# FLASHLIGHT_MAIN_SCH.net
KiCad netlist of a schematic drawn in Altium Designer
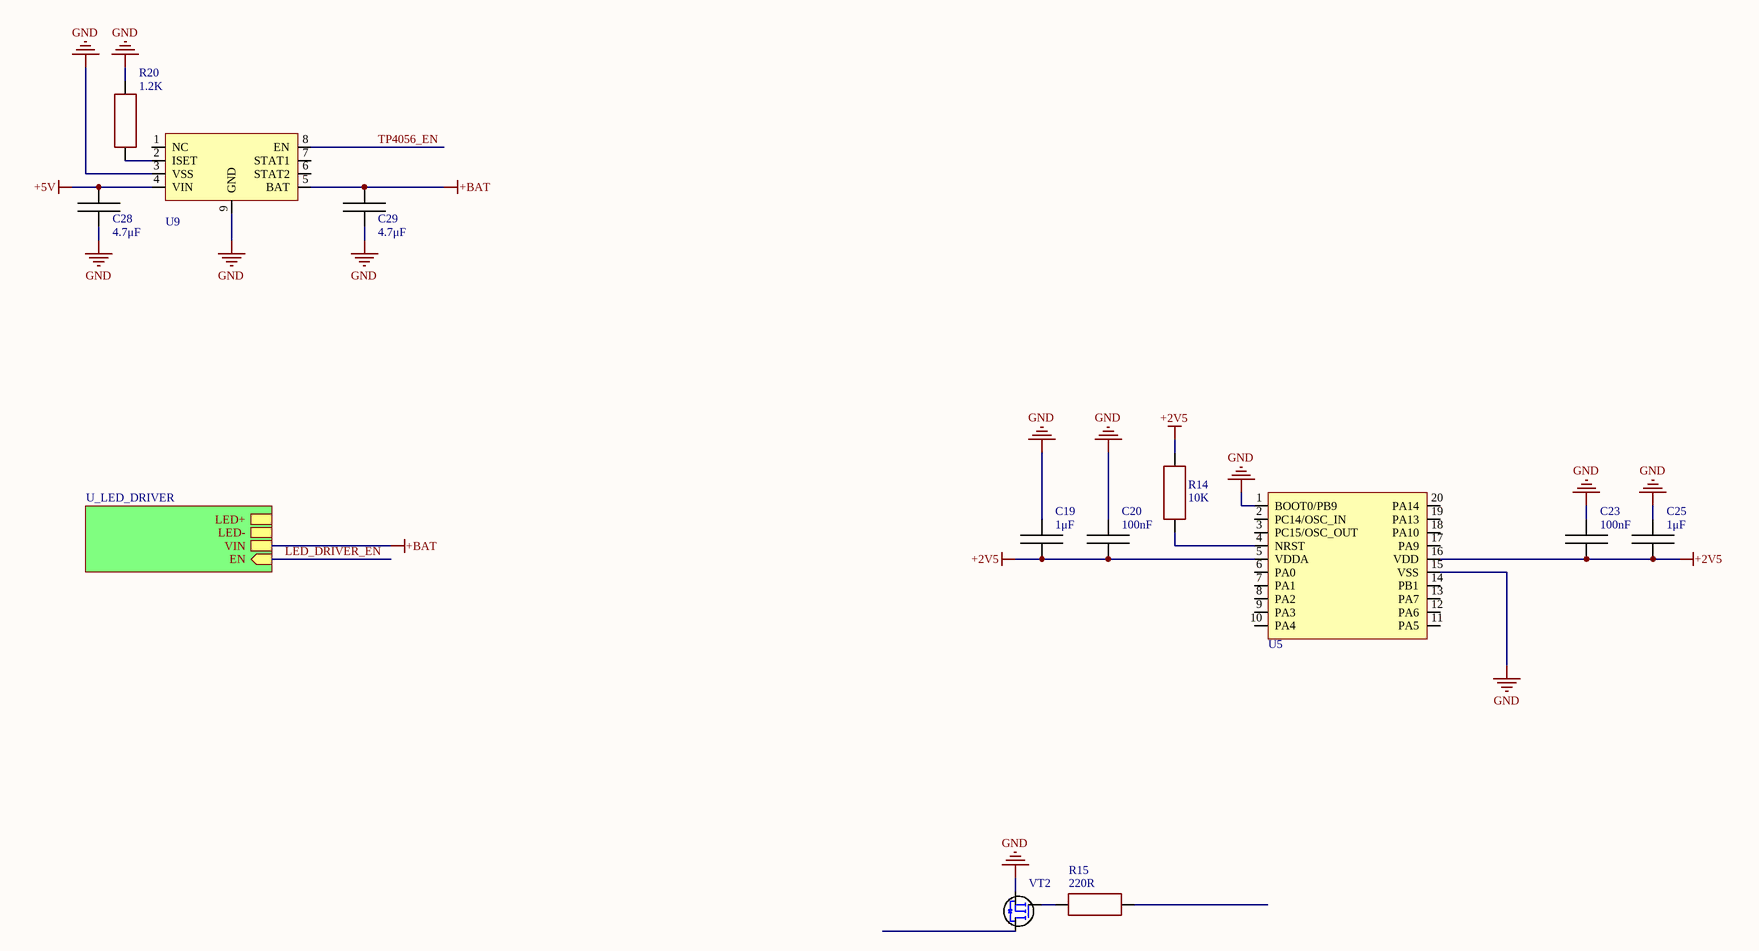
[diagram p0: FLASHLIGHT_MAIN_SCH.SchDoc]

(export (version "E")
  (design (tool "Eeschema 10.0.6"))
  (components
    (comp (ref "C19")
      (value "1μF")
      (footprint "CAP: 0402")
      (fields (field (name "VOLTAGE") "??V") (field (name "Comment") "Cap_0402"))
      (libsource (lib "capacitor") (part "Cap_0402"))
    )
    (comp (ref "C20")
      (value "100nF")
      (footprint "CAP: 0402")
      (fields (field (name "VOLTAGE") "??V") (field (name "Comment") "Cap_0402"))
      (libsource (lib "capacitor") (part "Cap_0402"))
    )
    (comp (ref "C23")
      (value "100nF")
      (footprint "CAP: 0402")
      (fields (field (name "VOLTAGE") "??V") (field (name "Comment") "Cap_0402"))
      (libsource (lib "capacitor") (part "Cap_0402"))
    )
    (comp (ref "C25")
      (value "1μF")
      (footprint "CAP: 0402")
      (fields (field (name "VOLTAGE") "??V") (field (name "Comment") "Cap_0402"))
      (libsource (lib "capacitor") (part "Cap_0402"))
    )
    (comp (ref "C28")
      (value "4.7μF")
      (footprint "CAP: 0402")
      (fields (field (name "VOLTAGE") "X5R 6.3В 20%") (field (name "Comment") "Cap_0402"))
      (libsource (lib "capacitor") (part "Cap_0402"))
    )
    (comp (ref "C29")
      (value "4.7μF")
      (footprint "CAP: 0402")
      (fields (field (name "VOLTAGE") "X5R 6.3В 20%") (field (name "Comment") "Cap_0402"))
      (libsource (lib "capacitor") (part "Cap_0402"))
    )
    (comp (ref "R14")
      (value "10K")
      (footprint "standard-case:RES: 0402")
      (fields (field (name "TOLERANCE") "±5%"))
      (libsource (lib "resistor") (part "Resistor_0402"))
    )
    (comp (ref "R15")
      (value "220R")
      (footprint "standard-case:RES: 0402")
      (fields (field (name "TOLERANCE") "±5%"))
      (libsource (lib "") (part "Resistor_0402_1"))
    )
    (comp (ref "R20")
      (value "1.2K")
      (footprint "RES: 0402")
      (fields (field (name "TOLERANCE") "±5%"))
      (libsource (lib "") (part "Resistor_0402_2"))
    )
    (comp (ref "U5")
      (value "STM32L011F4P6TR")
      (footprint "TSSOP-20")
      (fields (field (name "MANUFACTURER") "STMicroelectronics"))
      (libsource (lib "MY_INT_LIB") (part "STM32L011F4P6TR"))
    )
    (comp (ref "U9")
      (value "TP4056")
      (footprint "ESOP-8")
      (description "1s charge module")
      (fields (field (name "MANUFACTURER") "UMW"))
      (libsource (lib "MY_INT_LIB") (part "TP4056"))
    )
    (comp (ref "VT2")
      (value "IRLML6344")
      (footprint "SOT-23-3")
      (description "MOSFET N-CHANNEL 30V 5A")
      (fields (field (name "MANUFACTURER") "Fairchild"))
      (libsource (lib "MY_INT_LIB") (part "IRLML6344"))
    )
  )
  (nets
    (net (code "1") (name "+2V5") (class "Default")
      (node (ref "C19") (pin "1") (pinfunction "1_1") (pintype "passive"))
      (node (ref "C20") (pin "2") (pinfunction "2_2") (pintype "passive"))
      (node (ref "C23") (pin "2") (pinfunction "2_2") (pintype "passive"))
      (node (ref "C25") (pin "1") (pinfunction "1_1") (pintype "passive"))
      (node (ref "R14") (pin "1") (pinfunction "1_1") (pintype "passive"))
      (node (ref "U5") (pin "16") (pinfunction "VDD_16") (pintype "power_in"))
      (node (ref "U5") (pin "5") (pinfunction "VDDA_5") (pintype "power_in"))
    )
    (net (code "2") (name "+5V") (class "Default")
      (node (ref "C28") (pin "2") (pinfunction "2_2") (pintype "passive"))
      (node (ref "U9") (pin "4") (pinfunction "VIN_4") (pintype "passive"))
    )
    (net (code "3") (name "+BAT") (class "Default")
      (node (ref "C29") (pin "2") (pinfunction "2_2") (pintype "passive"))
      (node (ref "U9") (pin "5") (pinfunction "BAT_5") (pintype "passive"))
    )
    (net (code "7") (name "/TP4056_EN") (class "Default")
      (node (ref "U9") (pin "8") (pinfunction "EN_8") (pintype "passive"))
    )
    (net (code "8") (name "GND") (class "Default")
      (node (ref "C19") (pin "2") (pinfunction "2_2") (pintype "passive"))
      (node (ref "C20") (pin "1") (pinfunction "1_1") (pintype "passive"))
      (node (ref "C23") (pin "1") (pinfunction "1_1") (pintype "passive"))
      (node (ref "C25") (pin "2") (pinfunction "2_2") (pintype "passive"))
      (node (ref "C28") (pin "1") (pinfunction "1_1") (pintype "passive"))
      (node (ref "C29") (pin "1") (pinfunction "1_1") (pintype "passive"))
      (node (ref "R20") (pin "2") (pinfunction "2_2") (pintype "passive"))
      (node (ref "U5") (pin "1") (pinfunction "BOOT0/PB9_1") (pintype "passive"))
      (node (ref "U5") (pin "15") (pinfunction "VSS_15") (pintype "power_in"))
      (node (ref "U9") (pin "3") (pinfunction "VSS_3") (pintype "passive"))
      (node (ref "U9") (pin "9") (pinfunction "GND_9") (pintype "passive"))
      (node (ref "VT2") (pin "2") (pintype "power_in"))
    )
    (net (code "9") (name "Net-(R15-Pad1)") (class "Default")
      (node (ref "R15") (pin "1") (pinfunction "1_1") (pintype "passive"))
      (node (ref "VT2") (pin "1") (pintype "power_in"))
    )
    (net (code "10") (name "Net-(U5-NRST)") (class "Default")
      (node (ref "R14") (pin "2") (pinfunction "2_2") (pintype "passive"))
      (node (ref "U5") (pin "4") (pinfunction "NRST_4") (pintype "passive"))
    )
    (net (code "11") (name "Net-(U9-ISET)") (class "Default")
      (node (ref "R20") (pin "1") (pinfunction "1_1") (pintype "passive"))
      (node (ref "U9") (pin "2") (pinfunction "ISET_2") (pintype "passive"))
    )
    (net (code "12") (name "unconnected-(R15-Pad2)") (class "Default")
      (node (ref "R15") (pin "2") (pinfunction "2_2") (pintype "passive"))
    )
    (net (code "13") (name "unconnected-(U5-PA0-Pad6)") (class "Default")
      (node (ref "U5") (pin "6") (pinfunction "PA0_6") (pintype "passive"))
    )
    (net (code "14") (name "unconnected-(U5-PA1-Pad7)") (class "Default")
      (node (ref "U5") (pin "7") (pinfunction "PA1_7") (pintype "passive"))
    )
    (net (code "15") (name "unconnected-(U5-PA2-Pad8)") (class "Default")
      (node (ref "U5") (pin "8") (pinfunction "PA2_8") (pintype "passive"))
    )
    (net (code "16") (name "unconnected-(U5-PA3-Pad9)") (class "Default")
      (node (ref "U5") (pin "9") (pinfunction "PA3_9") (pintype "passive"))
    )
    (net (code "17") (name "unconnected-(U5-PA4-Pad10)") (class "Default")
      (node (ref "U5") (pin "10") (pinfunction "PA4_10") (pintype "passive"))
    )
    (net (code "18") (name "unconnected-(U5-PA5-Pad11)") (class "Default")
      (node (ref "U5") (pin "11") (pinfunction "PA5_11") (pintype "passive"))
    )
    (net (code "19") (name "unconnected-(U5-PA6-Pad12)") (class "Default")
      (node (ref "U5") (pin "12") (pinfunction "PA6_12") (pintype "passive"))
    )
    (net (code "20") (name "unconnected-(U5-PA7-Pad13)") (class "Default")
      (node (ref "U5") (pin "13") (pinfunction "PA7_13") (pintype "passive"))
    )
    (net (code "21") (name "unconnected-(U5-PA9-Pad17)") (class "Default")
      (node (ref "U5") (pin "17") (pinfunction "PA9_17") (pintype "passive"))
    )
    (net (code "22") (name "unconnected-(U5-PA10-Pad18)") (class "Default")
      (node (ref "U5") (pin "18") (pinfunction "PA10_18") (pintype "passive"))
    )
    (net (code "23") (name "unconnected-(U5-PA13-Pad19)") (class "Default")
      (node (ref "U5") (pin "19") (pinfunction "PA13_19") (pintype "passive"))
    )
    (net (code "24") (name "unconnected-(U5-PA14-Pad20)") (class "Default")
      (node (ref "U5") (pin "20") (pinfunction "PA14_20") (pintype "passive"))
    )
    (net (code "25") (name "unconnected-(U5-PB1-Pad14)") (class "Default")
      (node (ref "U5") (pin "14") (pinfunction "PB1_14") (pintype "passive"))
    )
    (net (code "26") (name "unconnected-(U5-PC14{slash}OSC_IN-Pad2)") (class "Default")
      (node (ref "U5") (pin "2") (pinfunction "PC14/OSC_IN_2") (pintype "passive"))
    )
    (net (code "27") (name "unconnected-(U5-PC15{slash}OSC_OUT-Pad3)") (class "Default")
      (node (ref "U5") (pin "3") (pinfunction "PC15/OSC_OUT_3") (pintype "passive"))
    )
    (net (code "28") (name "unconnected-(U9-NC-Pad1)") (class "Default")
      (node (ref "U9") (pin "1") (pinfunction "NC_1") (pintype "passive"))
    )
    (net (code "29") (name "unconnected-(U9-STAT1-Pad7)") (class "Default")
      (node (ref "U9") (pin "7") (pinfunction "STAT1_7") (pintype "passive"))
    )
    (net (code "30") (name "unconnected-(U9-STAT2-Pad6)") (class "Default")
      (node (ref "U9") (pin "6") (pinfunction "STAT2_6") (pintype "passive"))
    )
    (net (code "31") (name "unconnected-(VT2-Pad3)") (class "Default")
      (node (ref "VT2") (pin "3") (pintype "power_in"))
    )
  )
)
